# dartBoardV1.net
KiCad netlist of a schematic drawn in EAGLE
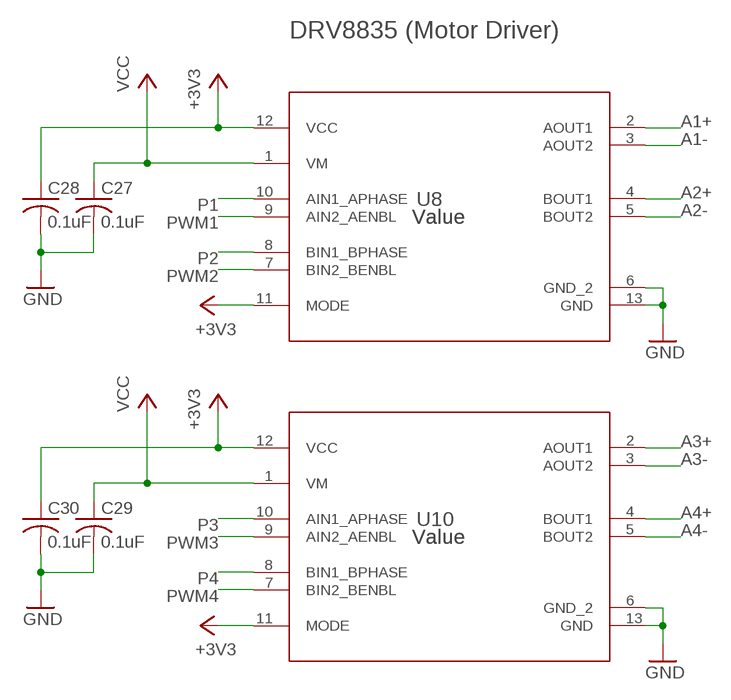
[diagram p0: schematic, sheet 1, part 1 of 2]
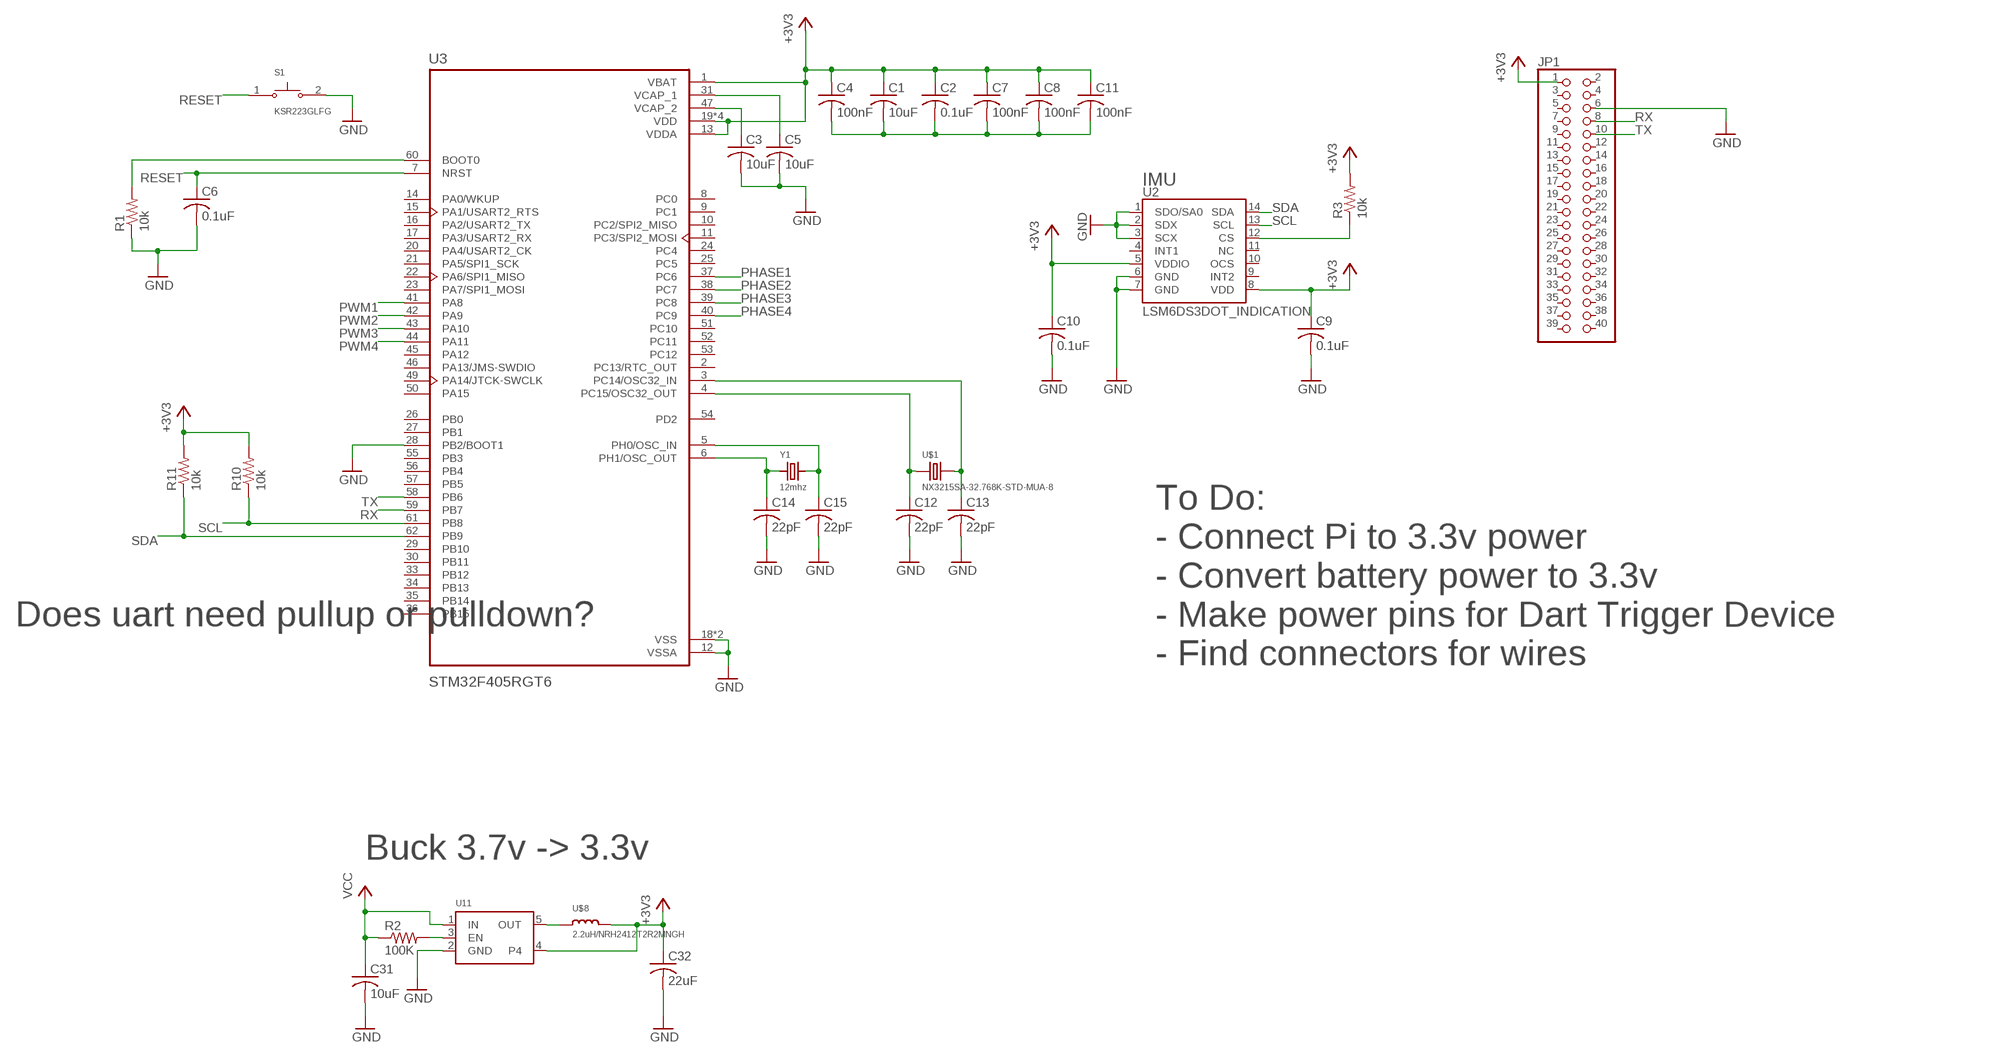
[diagram p1: schematic, sheet 1, part 2 of 2]

(export (version "E")
  (design (tool "Eeschema 10.0.6"))
  (components
    (comp (ref "C1")
      (value "10uF")
      (footprint "eagle-import:C0603")
      (libsource (lib "eagle-import") (part "C-USC0603"))
    )
    (comp (ref "C2")
      (value "0.1uF")
      (footprint "eagle-import:C0603")
      (libsource (lib "eagle-import") (part "C-USC0603"))
    )
    (comp (ref "C3")
      (value "10uF")
      (footprint "eagle-import:C0603")
      (libsource (lib "eagle-import") (part "C-USC0603"))
    )
    (comp (ref "C4")
      (value "100nF")
      (footprint "eagle-import:C0603")
      (libsource (lib "eagle-import") (part "C-USC0603"))
    )
    (comp (ref "C5")
      (value "10uF")
      (footprint "eagle-import:C0603")
      (libsource (lib "eagle-import") (part "C-USC0603"))
    )
    (comp (ref "C6")
      (value "0.1uF")
      (footprint "eagle-import:C0603")
      (libsource (lib "eagle-import") (part "C-USC0603"))
    )
    (comp (ref "C7")
      (value "100nF")
      (footprint "eagle-import:C0603")
      (libsource (lib "eagle-import") (part "C-USC0603"))
    )
    (comp (ref "C8")
      (value "100nF")
      (footprint "eagle-import:C0603")
      (libsource (lib "eagle-import") (part "C-USC0603"))
    )
    (comp (ref "C9")
      (value "0.1uF")
      (footprint "eagle-import:C0603")
      (libsource (lib "eagle-import") (part "C-USC0603"))
    )
    (comp (ref "C10")
      (value "0.1uF")
      (footprint "eagle-import:C0603")
      (libsource (lib "eagle-import") (part "C-USC0603"))
    )
    (comp (ref "C11")
      (value "100nF")
      (footprint "eagle-import:C0603")
      (libsource (lib "eagle-import") (part "C-USC0603"))
    )
    (comp (ref "C12")
      (value "22pF")
      (footprint "eagle-import:C0603")
      (libsource (lib "eagle-import") (part "C-USC0603"))
    )
    (comp (ref "C13")
      (value "22pF")
      (footprint "eagle-import:C0603")
      (libsource (lib "eagle-import") (part "C-USC0603"))
    )
    (comp (ref "C14")
      (value "22pF")
      (footprint "eagle-import:C0603")
      (libsource (lib "eagle-import") (part "C-USC0603"))
    )
    (comp (ref "C15")
      (value "22pF")
      (footprint "eagle-import:C0603")
      (libsource (lib "eagle-import") (part "C-USC0603"))
    )
    (comp (ref "C27")
      (value "0.1uF")
      (footprint "eagle-import:C0603")
      (libsource (lib "eagle-import") (part "C-USC0603"))
    )
    (comp (ref "C28")
      (value "0.1uF")
      (footprint "eagle-import:C0603")
      (libsource (lib "eagle-import") (part "C-USC0603"))
    )
    (comp (ref "C29")
      (value "0.1uF")
      (footprint "eagle-import:C0603")
      (libsource (lib "eagle-import") (part "C-USC0603"))
    )
    (comp (ref "C30")
      (value "0.1uF")
      (footprint "eagle-import:C0603")
      (libsource (lib "eagle-import") (part "C-USC0603"))
    )
    (comp (ref "C31")
      (value "10uF")
      (footprint "eagle-import:C0603")
      (libsource (lib "eagle-import") (part "C-USC0603"))
    )
    (comp (ref "C32")
      (value "22uF")
      (footprint "eagle-import:C0603")
      (libsource (lib "eagle-import") (part "C-USC0603"))
    )
    (comp (ref "JP1")
      (value "PINHD-2X20")
      (footprint "eagle-import:2X20")
      (libsource (lib "eagle-import") (part "PINHD-2X20"))
    )
    (comp (ref "R1")
      (value "10k")
      (footprint "eagle-import:R0603")
      (libsource (lib "eagle-import") (part "R-US_R0603"))
    )
    (comp (ref "R2")
      (value "100K")
      (footprint "eagle-import:R0603")
      (libsource (lib "eagle-import") (part "R-US_R0603"))
    )
    (comp (ref "R3")
      (value "10k")
      (footprint "eagle-import:R0603")
      (libsource (lib "eagle-import") (part "R-US_R0603"))
    )
    (comp (ref "R10")
      (value "10k")
      (footprint "eagle-import:R0603")
      (libsource (lib "eagle-import") (part "R-US_R0603"))
    )
    (comp (ref "R11")
      (value "10k")
      (footprint "eagle-import:R0603")
      (libsource (lib "eagle-import") (part "R-US_R0603"))
    )
    (comp (ref "S1")
      (value "KSR223GLFG")
      (footprint "eagle-import:SW_KSR223GLFG")
      (fields (field (name "DIGI-KEY_PART_NUMBER") "401-1704-1-ND") (field (name "MF") "C&K"))
      (libsource (lib "eagle-import") (part "KSR223GLFG"))
    )
    (comp (ref "U$1")
      (value "NX3215SA-32.768K-STD-MUA-8")
      (footprint "eagle-import:NX3215SA-32.768K-STD-MUA-8")
      (libsource (lib "eagle-import") (part "NX3215SA-32.768K-STD-MUA-8"))
    )
    (comp (ref "U$8")
      (value "2.2uH/NRH2412T2R2MNGH")
      (footprint "eagle-import:MDKK1616T2R2MM")
      (libsource (lib "eagle-import") (part "MDKK1616T2R2MM"))
    )
    (comp (ref "U2")
      (value "LSM6DS3DOT_INDICATION")
      (footprint "eagle-import:LGA14L_DOT_INDICATOR")
      (libsource (lib "eagle-import") (part "LSM6DS3DOT_INDICATION"))
    )
    (comp (ref "U3")
      (value "STM32F405RGT6")
      (footprint "eagle-import:QFP50P1200X1200X160-64N")
      (fields (field (name "DIGI-KEY_PART_NUMBER") "497-11767-ND") (field (name "MF") "STMicroelectronics"))
      (libsource (lib "eagle-import") (part "STM32F405RGT6"))
    )
    (comp (ref "U8")
      (value "Value")
      (footprint "eagle-import:DSS0012A")
      (fields (field (name "MANUFACTURER") "Texas Instruments") (field (name "PARTNUMBER") "DRV8835DSSR"))
      (libsource (lib "eagle-import") (part "DRV8835DSSR"))
    )
    (comp (ref "U10")
      (value "Value")
      (footprint "eagle-import:DSS0012A")
      (fields (field (name "MANUFACTURER") "Texas Instruments") (field (name "PARTNUMBER") "DRV8835DSSR"))
      (libsource (lib "eagle-import") (part "DRV8835DSSR"))
    )
    (comp (ref "U11")
      (value "VREG_SOT23-5")
      (footprint "eagle-import:SOT23-5")
      (libsource (lib "eagle-import") (part "VREG_SOT23-5"))
    )
    (comp (ref "Y1")
      (value "12mhz")
      (footprint "eagle-import:CRYSTAL_2.5X2")
      (libsource (lib "eagle-import") (part "CRYSTAL2.5X2.0MM"))
    )
  )
  (nets
    (net (code "1") (name "+3V3") (class "Default")
      (node (ref "C1") (pin "1") (pinfunction "1_1") (pintype "passive"))
      (node (ref "C10") (pin "1") (pinfunction "1_1") (pintype "passive"))
      (node (ref "C11") (pin "1") (pinfunction "1_1") (pintype "passive"))
      (node (ref "C2") (pin "1") (pinfunction "1_1") (pintype "passive"))
      (node (ref "C28") (pin "1") (pinfunction "1_1") (pintype "passive"))
      (node (ref "C30") (pin "1") (pinfunction "1_1") (pintype "passive"))
      (node (ref "C32") (pin "1") (pinfunction "1_1") (pintype "passive"))
      (node (ref "C4") (pin "1") (pinfunction "1_1") (pintype "passive"))
      (node (ref "C7") (pin "1") (pinfunction "1_1") (pintype "passive"))
      (node (ref "C8") (pin "1") (pinfunction "1_1") (pintype "passive"))
      (node (ref "C9") (pin "1") (pinfunction "1_1") (pintype "passive"))
      (node (ref "JP1") (pin "1") (pinfunction "1_1") (pintype "passive"))
      (node (ref "R10") (pin "2") (pinfunction "2_2") (pintype "passive"))
      (node (ref "R11") (pin "2") (pinfunction "2_2") (pintype "passive"))
      (node (ref "R3") (pin "2") (pinfunction "2_2") (pintype "passive"))
      (node (ref "U$8") (pin "P$2") (pinfunction "2_P$2") (pintype "passive"))
      (node (ref "U10") (pin "11") (pinfunction "MODE_11") (pintype "input"))
      (node (ref "U10") (pin "12") (pinfunction "VCC_12") (pintype "power_in"))
      (node (ref "U11") (pin "4") (pinfunction "P4_4") (pintype "bidirectional"))
      (node (ref "U2") (pin "5") (pinfunction "VDDIO_5") (pintype "bidirectional"))
      (node (ref "U2") (pin "8") (pinfunction "VDD_8") (pintype "bidirectional"))
      (node (ref "U3") (pin "1") (pinfunction "VBAT_1") (pintype "power_in"))
      (node (ref "U3") (pin "13") (pinfunction "VDDA_13") (pintype "power_in"))
      (node (ref "U3") (pin "19") (pinfunction "VDD_19") (pintype "power_in"))
      (node (ref "U3") (pin "32") (pinfunction "VDD_32") (pintype "power_in"))
      (node (ref "U3") (pin "48") (pinfunction "VDD_48") (pintype "power_in"))
      (node (ref "U3") (pin "64") (pinfunction "VDD_64") (pintype "power_in"))
      (node (ref "U8") (pin "11") (pinfunction "MODE_11") (pintype "input"))
      (node (ref "U8") (pin "12") (pinfunction "VCC_12") (pintype "power_in"))
    )
    (net (code "2") (name "/A1+") (class "Default")
      (node (ref "U8") (pin "2") (pinfunction "AOUT1_2") (pintype "output"))
    )
    (net (code "3") (name "/A1-") (class "Default")
      (node (ref "U8") (pin "3") (pinfunction "AOUT2_3") (pintype "output"))
    )
    (net (code "4") (name "/A2+") (class "Default")
      (node (ref "U8") (pin "4") (pinfunction "BOUT1_4") (pintype "output"))
    )
    (net (code "5") (name "/A2-") (class "Default")
      (node (ref "U8") (pin "5") (pinfunction "BOUT2_5") (pintype "output"))
    )
    (net (code "6") (name "/A3+") (class "Default")
      (node (ref "U10") (pin "2") (pinfunction "AOUT1_2") (pintype "output"))
    )
    (net (code "7") (name "/A3-") (class "Default")
      (node (ref "U10") (pin "3") (pinfunction "AOUT2_3") (pintype "output"))
    )
    (net (code "8") (name "/A4+") (class "Default")
      (node (ref "U10") (pin "4") (pinfunction "BOUT1_4") (pintype "output"))
    )
    (net (code "9") (name "/A4-") (class "Default")
      (node (ref "U10") (pin "5") (pinfunction "BOUT2_5") (pintype "output"))
    )
    (net (code "10") (name "/P1") (class "Default")
      (node (ref "U8") (pin "10") (pinfunction "AIN1_APHASE_10") (pintype "input"))
    )
    (net (code "11") (name "/P2") (class "Default")
      (node (ref "U8") (pin "8") (pinfunction "BIN1_BPHASE_8") (pintype "input"))
    )
    (net (code "12") (name "/P3") (class "Default")
      (node (ref "U10") (pin "10") (pinfunction "AIN1_APHASE_10") (pintype "input"))
    )
    (net (code "13") (name "/P4") (class "Default")
      (node (ref "U10") (pin "8") (pinfunction "BIN1_BPHASE_8") (pintype "input"))
    )
    (net (code "14") (name "/PHASE1") (class "Default")
      (node (ref "U3") (pin "37") (pinfunction "PC6_37") (pintype "bidirectional"))
    )
    (net (code "15") (name "/PHASE2") (class "Default")
      (node (ref "U3") (pin "38") (pinfunction "PC7_38") (pintype "bidirectional"))
    )
    (net (code "16") (name "/PHASE3") (class "Default")
      (node (ref "U3") (pin "39") (pinfunction "PC8_39") (pintype "bidirectional"))
    )
    (net (code "17") (name "/PHASE4") (class "Default")
      (node (ref "U3") (pin "40") (pinfunction "PC9_40") (pintype "bidirectional"))
    )
    (net (code "18") (name "/PWM1") (class "Default")
      (node (ref "U3") (pin "41") (pinfunction "PA8_41") (pintype "bidirectional"))
      (node (ref "U8") (pin "9") (pinfunction "AIN2_AENBL_9") (pintype "input"))
    )
    (net (code "19") (name "/PWM2") (class "Default")
      (node (ref "U3") (pin "42") (pinfunction "PA9_42") (pintype "bidirectional"))
      (node (ref "U8") (pin "7") (pinfunction "BIN2_BENBL_7") (pintype "input"))
    )
    (net (code "20") (name "/PWM3") (class "Default")
      (node (ref "U10") (pin "9") (pinfunction "AIN2_AENBL_9") (pintype "input"))
      (node (ref "U3") (pin "43") (pinfunction "PA10_43") (pintype "bidirectional"))
    )
    (net (code "21") (name "/PWM4") (class "Default")
      (node (ref "U10") (pin "7") (pinfunction "BIN2_BENBL_7") (pintype "input"))
      (node (ref "U3") (pin "44") (pinfunction "PA11_44") (pintype "bidirectional"))
    )
    (net (code "22") (name "/RESET") (class "Default")
      (node (ref "C6") (pin "1") (pinfunction "1_1") (pintype "passive"))
      (node (ref "S1") (pin "1") (pinfunction "1_1") (pintype "passive"))
      (node (ref "U3") (pin "7") (pinfunction "NRST_7") (pintype "bidirectional"))
    )
    (net (code "23") (name "/RX") (class "Default")
      (node (ref "JP1") (pin "8") (pinfunction "8_8") (pintype "passive"))
      (node (ref "U3") (pin "59") (pinfunction "PB7_59") (pintype "bidirectional"))
    )
    (net (code "24") (name "/SCL") (class "Default")
      (node (ref "R10") (pin "1") (pinfunction "1_1") (pintype "passive"))
      (node (ref "U2") (pin "13") (pinfunction "SCL_13") (pintype "bidirectional"))
      (node (ref "U3") (pin "61") (pinfunction "PB8_61") (pintype "bidirectional"))
    )
    (net (code "25") (name "/SDA") (class "Default")
      (node (ref "R11") (pin "1") (pinfunction "1_1") (pintype "passive"))
      (node (ref "U2") (pin "14") (pinfunction "SDA_14") (pintype "bidirectional"))
      (node (ref "U3") (pin "62") (pinfunction "PB9_62") (pintype "bidirectional"))
    )
    (net (code "26") (name "/TX") (class "Default")
      (node (ref "JP1") (pin "10") (pinfunction "10_10") (pintype "passive"))
      (node (ref "U3") (pin "58") (pinfunction "PB6_58") (pintype "bidirectional"))
    )
    (net (code "27") (name "GND") (class "Default")
      (node (ref "C10") (pin "2") (pinfunction "2_2") (pintype "passive"))
      (node (ref "C12") (pin "2") (pinfunction "2_2") (pintype "passive"))
      (node (ref "C13") (pin "2") (pinfunction "2_2") (pintype "passive"))
      (node (ref "C14") (pin "2") (pinfunction "2_2") (pintype "passive"))
      (node (ref "C15") (pin "2") (pinfunction "2_2") (pintype "passive"))
      (node (ref "C27") (pin "2") (pinfunction "2_2") (pintype "passive"))
      (node (ref "C28") (pin "2") (pinfunction "2_2") (pintype "passive"))
      (node (ref "C29") (pin "2") (pinfunction "2_2") (pintype "passive"))
      (node (ref "C3") (pin "2") (pinfunction "2_2") (pintype "passive"))
      (node (ref "C30") (pin "2") (pinfunction "2_2") (pintype "passive"))
      (node (ref "C31") (pin "2") (pinfunction "2_2") (pintype "passive"))
      (node (ref "C32") (pin "2") (pinfunction "2_2") (pintype "passive"))
      (node (ref "C5") (pin "2") (pinfunction "2_2") (pintype "passive"))
      (node (ref "C6") (pin "2") (pinfunction "2_2") (pintype "passive"))
      (node (ref "C9") (pin "2") (pinfunction "2_2") (pintype "passive"))
      (node (ref "JP1") (pin "6") (pinfunction "6_6") (pintype "passive"))
      (node (ref "R1") (pin "1") (pinfunction "1_1") (pintype "passive"))
      (node (ref "S1") (pin "2") (pinfunction "2_2") (pintype "passive"))
      (node (ref "U10") (pin "13") (pinfunction "GND_13") (pintype "power_in"))
      (node (ref "U10") (pin "6") (pinfunction "GND_2_6") (pintype "power_in"))
      (node (ref "U11") (pin "2") (pinfunction "GND_2") (pintype "bidirectional"))
      (node (ref "U2") (pin "1") (pinfunction "SDO/SA0_1") (pintype "bidirectional"))
      (node (ref "U2") (pin "2") (pinfunction "SDX_2") (pintype "bidirectional"))
      (node (ref "U2") (pin "3") (pinfunction "SCX_3") (pintype "bidirectional"))
      (node (ref "U2") (pin "6") (pinfunction "GND_6") (pintype "bidirectional"))
      (node (ref "U2") (pin "7") (pinfunction "GND_7") (pintype "bidirectional"))
      (node (ref "U3") (pin "12") (pinfunction "VSSA_12") (pintype "power_in"))
      (node (ref "U3") (pin "18") (pinfunction "VSS_18") (pintype "power_in"))
      (node (ref "U3") (pin "28") (pinfunction "PB2/BOOT1_28") (pintype "bidirectional"))
      (node (ref "U3") (pin "63") (pinfunction "VSS_63") (pintype "power_in"))
      (node (ref "U8") (pin "13") (pinfunction "GND_13") (pintype "power_in"))
      (node (ref "U8") (pin "6") (pinfunction "GND_2_6") (pintype "power_in"))
    )
    (net (code "28") (name "Net-(C1-Pad2)") (class "Default")
      (node (ref "C1") (pin "2") (pinfunction "2_2") (pintype "passive"))
      (node (ref "C11") (pin "2") (pinfunction "2_2") (pintype "passive"))
      (node (ref "C2") (pin "2") (pinfunction "2_2") (pintype "passive"))
      (node (ref "C4") (pin "2") (pinfunction "2_2") (pintype "passive"))
      (node (ref "C7") (pin "2") (pinfunction "2_2") (pintype "passive"))
      (node (ref "C8") (pin "2") (pinfunction "2_2") (pintype "passive"))
    )
    (net (code "29") (name "Net-(U$1-1)") (class "Default")
      (node (ref "C12") (pin "1") (pinfunction "1_1") (pintype "passive"))
      (node (ref "U$1") (pin "P$1") (pinfunction "1_P$1") (pintype "passive"))
      (node (ref "U3") (pin "4") (pinfunction "PC15/OSC32_OUT_4") (pintype "bidirectional"))
    )
    (net (code "30") (name "Net-(U$1-2)") (class "Default")
      (node (ref "C13") (pin "1") (pinfunction "1_1") (pintype "passive"))
      (node (ref "U$1") (pin "P$2") (pinfunction "2_P$2") (pintype "passive"))
      (node (ref "U3") (pin "3") (pinfunction "PC14/OSC32_IN_3") (pintype "bidirectional"))
    )
    (net (code "31") (name "Net-(U$8-1)") (class "Default")
      (node (ref "U$8") (pin "P$1") (pinfunction "1_P$1") (pintype "passive"))
      (node (ref "U11") (pin "5") (pinfunction "OUT_5") (pintype "bidirectional"))
    )
    (net (code "32") (name "Net-(U2-CS)") (class "Default")
      (node (ref "R3") (pin "1") (pinfunction "1_1") (pintype "passive"))
      (node (ref "U2") (pin "12") (pinfunction "CS_12") (pintype "bidirectional"))
    )
    (net (code "33") (name "Net-(U3-BOOT0)") (class "Default")
      (node (ref "R1") (pin "2") (pinfunction "2_2") (pintype "passive"))
      (node (ref "U3") (pin "60") (pinfunction "BOOT0_60") (pintype "bidirectional"))
    )
    (net (code "34") (name "Net-(U3-PH0{slash}OSC_IN)") (class "Default")
      (node (ref "C15") (pin "1") (pinfunction "1_1") (pintype "passive"))
      (node (ref "U3") (pin "5") (pinfunction "PH0/OSC_IN_5") (pintype "bidirectional"))
      (node (ref "Y1") (pin "3") (pinfunction "2_3") (pintype "passive"))
    )
    (net (code "35") (name "Net-(U3-PH1{slash}OSC_OUT)") (class "Default")
      (node (ref "C14") (pin "1") (pinfunction "1_1") (pintype "passive"))
      (node (ref "U3") (pin "6") (pinfunction "PH1/OSC_OUT_6") (pintype "bidirectional"))
      (node (ref "Y1") (pin "1") (pinfunction "1_1") (pintype "passive"))
    )
    (net (code "36") (name "Net-(U3-VCAP_1)") (class "Default")
      (node (ref "C5") (pin "1") (pinfunction "1_1") (pintype "passive"))
      (node (ref "U3") (pin "31") (pinfunction "VCAP_1_31") (pintype "power_in"))
    )
    (net (code "37") (name "Net-(U3-VCAP_2)") (class "Default")
      (node (ref "C3") (pin "1") (pinfunction "1_1") (pintype "passive"))
      (node (ref "U3") (pin "47") (pinfunction "VCAP_2_47") (pintype "power_in"))
    )
    (net (code "38") (name "Net-(U11-EN)") (class "Default")
      (node (ref "R2") (pin "2") (pinfunction "2_2") (pintype "passive"))
      (node (ref "U11") (pin "3") (pinfunction "EN_3") (pintype "bidirectional"))
    )
    (net (code "39") (name "VCC") (class "Default")
      (node (ref "C27") (pin "1") (pinfunction "1_1") (pintype "passive"))
      (node (ref "C29") (pin "1") (pinfunction "1_1") (pintype "passive"))
      (node (ref "C31") (pin "1") (pinfunction "1_1") (pintype "passive"))
      (node (ref "R2") (pin "1") (pinfunction "1_1") (pintype "passive"))
      (node (ref "U10") (pin "1") (pinfunction "VM_1") (pintype "power_in"))
      (node (ref "U11") (pin "1") (pinfunction "IN_1") (pintype "bidirectional"))
      (node (ref "U8") (pin "1") (pinfunction "VM_1") (pintype "power_in"))
    )
    (net (code "40") (name "unconnected-(JP1-Pad2)") (class "Default")
      (node (ref "JP1") (pin "2") (pinfunction "2_2") (pintype "passive"))
    )
    (net (code "41") (name "unconnected-(JP1-Pad3)") (class "Default")
      (node (ref "JP1") (pin "3") (pinfunction "3_3") (pintype "passive"))
    )
    (net (code "42") (name "unconnected-(JP1-Pad4)") (class "Default")
      (node (ref "JP1") (pin "4") (pinfunction "4_4") (pintype "passive"))
    )
    (net (code "43") (name "unconnected-(JP1-Pad5)") (class "Default")
      (node (ref "JP1") (pin "5") (pinfunction "5_5") (pintype "passive"))
    )
    (net (code "44") (name "unconnected-(JP1-Pad7)") (class "Default")
      (node (ref "JP1") (pin "7") (pinfunction "7_7") (pintype "passive"))
    )
    (net (code "45") (name "unconnected-(JP1-Pad9)") (class "Default")
      (node (ref "JP1") (pin "9") (pinfunction "9_9") (pintype "passive"))
    )
    (net (code "46") (name "unconnected-(JP1-Pad11)") (class "Default")
      (node (ref "JP1") (pin "11") (pinfunction "11_11") (pintype "passive"))
    )
    (net (code "47") (name "unconnected-(JP1-Pad12)") (class "Default")
      (node (ref "JP1") (pin "12") (pinfunction "12_12") (pintype "passive"))
    )
    (net (code "48") (name "unconnected-(JP1-Pad13)") (class "Default")
      (node (ref "JP1") (pin "13") (pinfunction "13_13") (pintype "passive"))
    )
    (net (code "49") (name "unconnected-(JP1-Pad14)") (class "Default")
      (node (ref "JP1") (pin "14") (pinfunction "14_14") (pintype "passive"))
    )
    (net (code "50") (name "unconnected-(JP1-Pad15)") (class "Default")
      (node (ref "JP1") (pin "15") (pinfunction "15_15") (pintype "passive"))
    )
    (net (code "51") (name "unconnected-(JP1-Pad16)") (class "Default")
      (node (ref "JP1") (pin "16") (pinfunction "16_16") (pintype "passive"))
    )
    (net (code "52") (name "unconnected-(JP1-Pad17)") (class "Default")
      (node (ref "JP1") (pin "17") (pinfunction "17_17") (pintype "passive"))
    )
    (net (code "53") (name "unconnected-(JP1-Pad18)") (class "Default")
      (node (ref "JP1") (pin "18") (pinfunction "18_18") (pintype "passive"))
    )
    (net (code "54") (name "unconnected-(JP1-Pad19)") (class "Default")
      (node (ref "JP1") (pin "19") (pinfunction "19_19") (pintype "passive"))
    )
    (net (code "55") (name "unconnected-(JP1-Pad20)") (class "Default")
      (node (ref "JP1") (pin "20") (pinfunction "20_20") (pintype "passive"))
    )
    (net (code "56") (name "unconnected-(JP1-Pad21)") (class "Default")
      (node (ref "JP1") (pin "21") (pinfunction "21_21") (pintype "passive"))
    )
    (net (code "57") (name "unconnected-(JP1-Pad22)") (class "Default")
      (node (ref "JP1") (pin "22") (pinfunction "22_22") (pintype "passive"))
    )
    (net (code "58") (name "unconnected-(JP1-Pad23)") (class "Default")
      (node (ref "JP1") (pin "23") (pinfunction "23_23") (pintype "passive"))
    )
    (net (code "59") (name "unconnected-(JP1-Pad24)") (class "Default")
      (node (ref "JP1") (pin "24") (pinfunction "24_24") (pintype "passive"))
    )
    (net (code "60") (name "unconnected-(JP1-Pad25)") (class "Default")
      (node (ref "JP1") (pin "25") (pinfunction "25_25") (pintype "passive"))
    )
    (net (code "61") (name "unconnected-(JP1-Pad26)") (class "Default")
      (node (ref "JP1") (pin "26") (pinfunction "26_26") (pintype "passive"))
    )
    (net (code "62") (name "unconnected-(JP1-Pad27)") (class "Default")
      (node (ref "JP1") (pin "27") (pinfunction "27_27") (pintype "passive"))
    )
    (net (code "63") (name "unconnected-(JP1-Pad28)") (class "Default")
      (node (ref "JP1") (pin "28") (pinfunction "28_28") (pintype "passive"))
    )
    (net (code "64") (name "unconnected-(JP1-Pad29)") (class "Default")
      (node (ref "JP1") (pin "29") (pinfunction "29_29") (pintype "passive"))
    )
    (net (code "65") (name "unconnected-(JP1-Pad30)") (class "Default")
      (node (ref "JP1") (pin "30") (pinfunction "30_30") (pintype "passive"))
    )
    (net (code "66") (name "unconnected-(JP1-Pad31)") (class "Default")
      (node (ref "JP1") (pin "31") (pinfunction "31_31") (pintype "passive"))
    )
    (net (code "67") (name "unconnected-(JP1-Pad32)") (class "Default")
      (node (ref "JP1") (pin "32") (pinfunction "32_32") (pintype "passive"))
    )
    (net (code "68") (name "unconnected-(JP1-Pad33)") (class "Default")
      (node (ref "JP1") (pin "33") (pinfunction "33_33") (pintype "passive"))
    )
    (net (code "69") (name "unconnected-(JP1-Pad34)") (class "Default")
      (node (ref "JP1") (pin "34") (pinfunction "34_34") (pintype "passive"))
    )
    (net (code "70") (name "unconnected-(JP1-Pad35)") (class "Default")
      (node (ref "JP1") (pin "35") (pinfunction "35_35") (pintype "passive"))
    )
    (net (code "71") (name "unconnected-(JP1-Pad36)") (class "Default")
      (node (ref "JP1") (pin "36") (pinfunction "36_36") (pintype "passive"))
    )
    (net (code "72") (name "unconnected-(JP1-Pad37)") (class "Default")
      (node (ref "JP1") (pin "37") (pinfunction "37_37") (pintype "passive"))
    )
    (net (code "73") (name "unconnected-(JP1-Pad38)") (class "Default")
      (node (ref "JP1") (pin "38") (pinfunction "38_38") (pintype "passive"))
    )
    (net (code "74") (name "unconnected-(JP1-Pad39)") (class "Default")
      (node (ref "JP1") (pin "39") (pinfunction "39_39") (pintype "passive"))
    )
    (net (code "75") (name "unconnected-(JP1-Pad40)") (class "Default")
      (node (ref "JP1") (pin "40") (pinfunction "40_40") (pintype "passive"))
    )
    (net (code "76") (name "unconnected-(U2-INT1-Pad4)") (class "Default")
      (node (ref "U2") (pin "4") (pinfunction "INT1_4") (pintype "bidirectional"))
    )
    (net (code "77") (name "unconnected-(U2-INT2-Pad9)") (class "Default")
      (node (ref "U2") (pin "9") (pinfunction "INT2_9") (pintype "bidirectional"))
    )
    (net (code "78") (name "unconnected-(U2-NC-Pad11)") (class "Default")
      (node (ref "U2") (pin "11") (pinfunction "NC_11") (pintype "bidirectional"))
    )
    (net (code "79") (name "unconnected-(U2-OCS-Pad10)") (class "Default")
      (node (ref "U2") (pin "10") (pinfunction "OCS_10") (pintype "bidirectional"))
    )
    (net (code "80") (name "unconnected-(U3-PA0{slash}WKUP-Pad14)") (class "Default")
      (node (ref "U3") (pin "14") (pinfunction "PA0/WKUP_14") (pintype "bidirectional"))
    )
    (net (code "81") (name "unconnected-(U3-PA1{slash}USART2_RTS-Pad15)") (class "Default")
      (node (ref "U3") (pin "15") (pinfunction "PA1/USART2_RTS_15") (pintype "bidirectional"))
    )
    (net (code "82") (name "unconnected-(U3-PA2{slash}USART2_TX-Pad16)") (class "Default")
      (node (ref "U3") (pin "16") (pinfunction "PA2/USART2_TX_16") (pintype "bidirectional"))
    )
    (net (code "83") (name "unconnected-(U3-PA3{slash}USART2_RX-Pad17)") (class "Default")
      (node (ref "U3") (pin "17") (pinfunction "PA3/USART2_RX_17") (pintype "bidirectional"))
    )
    (net (code "84") (name "unconnected-(U3-PA4{slash}USART2_CK-Pad20)") (class "Default")
      (node (ref "U3") (pin "20") (pinfunction "PA4/USART2_CK_20") (pintype "bidirectional"))
    )
    (net (code "85") (name "unconnected-(U3-PA5{slash}SPI1_SCK-Pad21)") (class "Default")
      (node (ref "U3") (pin "21") (pinfunction "PA5/SPI1_SCK_21") (pintype "bidirectional"))
    )
    (net (code "86") (name "unconnected-(U3-PA6{slash}SPI1_MISO-Pad22)") (class "Default")
      (node (ref "U3") (pin "22") (pinfunction "PA6/SPI1_MISO_22") (pintype "bidirectional"))
    )
    (net (code "87") (name "unconnected-(U3-PA7{slash}SPI1_MOSI-Pad23)") (class "Default")
      (node (ref "U3") (pin "23") (pinfunction "PA7/SPI1_MOSI_23") (pintype "bidirectional"))
    )
    (net (code "88") (name "unconnected-(U3-PA12-Pad45)") (class "Default")
      (node (ref "U3") (pin "45") (pinfunction "PA12_45") (pintype "bidirectional"))
    )
    (net (code "89") (name "unconnected-(U3-PA13{slash}JMS-SWDIO-Pad46)") (class "Default")
      (node (ref "U3") (pin "46") (pinfunction "PA13/JMS-SWDIO_46") (pintype "bidirectional"))
    )
    (net (code "90") (name "unconnected-(U3-PA14{slash}JTCK-SWCLK-Pad49)") (class "Default")
      (node (ref "U3") (pin "49") (pinfunction "PA14/JTCK-SWCLK_49") (pintype "bidirectional"))
    )
    (net (code "91") (name "unconnected-(U3-PA15-Pad50)") (class "Default")
      (node (ref "U3") (pin "50") (pinfunction "PA15_50") (pintype "bidirectional"))
    )
    (net (code "92") (name "unconnected-(U3-PB0-Pad26)") (class "Default")
      (node (ref "U3") (pin "26") (pinfunction "PB0_26") (pintype "bidirectional"))
    )
    (net (code "93") (name "unconnected-(U3-PB1-Pad27)") (class "Default")
      (node (ref "U3") (pin "27") (pinfunction "PB1_27") (pintype "bidirectional"))
    )
    (net (code "94") (name "unconnected-(U3-PB3-Pad55)") (class "Default")
      (node (ref "U3") (pin "55") (pinfunction "PB3_55") (pintype "bidirectional"))
    )
    (net (code "95") (name "unconnected-(U3-PB4-Pad56)") (class "Default")
      (node (ref "U3") (pin "56") (pinfunction "PB4_56") (pintype "bidirectional"))
    )
    (net (code "96") (name "unconnected-(U3-PB5-Pad57)") (class "Default")
      (node (ref "U3") (pin "57") (pinfunction "PB5_57") (pintype "bidirectional"))
    )
    (net (code "97") (name "unconnected-(U3-PB10-Pad29)") (class "Default")
      (node (ref "U3") (pin "29") (pinfunction "PB10_29") (pintype "bidirectional"))
    )
    (net (code "98") (name "unconnected-(U3-PB11-Pad30)") (class "Default")
      (node (ref "U3") (pin "30") (pinfunction "PB11_30") (pintype "bidirectional"))
    )
    (net (code "99") (name "unconnected-(U3-PB12-Pad33)") (class "Default")
      (node (ref "U3") (pin "33") (pinfunction "PB12_33") (pintype "bidirectional"))
    )
    (net (code "100") (name "unconnected-(U3-PB13-Pad34)") (class "Default")
      (node (ref "U3") (pin "34") (pinfunction "PB13_34") (pintype "bidirectional"))
    )
    (net (code "101") (name "unconnected-(U3-PB14-Pad35)") (class "Default")
      (node (ref "U3") (pin "35") (pinfunction "PB14_35") (pintype "bidirectional"))
    )
    (net (code "102") (name "unconnected-(U3-PB15-Pad36)") (class "Default")
      (node (ref "U3") (pin "36") (pinfunction "PB15_36") (pintype "bidirectional"))
    )
    (net (code "103") (name "unconnected-(U3-PC0-Pad8)") (class "Default")
      (node (ref "U3") (pin "8") (pinfunction "PC0_8") (pintype "bidirectional"))
    )
    (net (code "104") (name "unconnected-(U3-PC1-Pad9)") (class "Default")
      (node (ref "U3") (pin "9") (pinfunction "PC1_9") (pintype "bidirectional"))
    )
    (net (code "105") (name "unconnected-(U3-PC2{slash}SPI2_MISO-Pad10)") (class "Default")
      (node (ref "U3") (pin "10") (pinfunction "PC2/SPI2_MISO_10") (pintype "bidirectional"))
    )
    (net (code "106") (name "unconnected-(U3-PC3{slash}SPI2_MOSI-Pad11)") (class "Default")
      (node (ref "U3") (pin "11") (pinfunction "PC3/SPI2_MOSI_11") (pintype "bidirectional"))
    )
    (net (code "107") (name "unconnected-(U3-PC4-Pad24)") (class "Default")
      (node (ref "U3") (pin "24") (pinfunction "PC4_24") (pintype "bidirectional"))
    )
    (net (code "108") (name "unconnected-(U3-PC5-Pad25)") (class "Default")
      (node (ref "U3") (pin "25") (pinfunction "PC5_25") (pintype "bidirectional"))
    )
    (net (code "109") (name "unconnected-(U3-PC10-Pad51)") (class "Default")
      (node (ref "U3") (pin "51") (pinfunction "PC10_51") (pintype "bidirectional"))
    )
    (net (code "110") (name "unconnected-(U3-PC11-Pad52)") (class "Default")
      (node (ref "U3") (pin "52") (pinfunction "PC11_52") (pintype "bidirectional"))
    )
    (net (code "111") (name "unconnected-(U3-PC12-Pad53)") (class "Default")
      (node (ref "U3") (pin "53") (pinfunction "PC12_53") (pintype "bidirectional"))
    )
    (net (code "112") (name "unconnected-(U3-PC13{slash}RTC_OUT-Pad2)") (class "Default")
      (node (ref "U3") (pin "2") (pinfunction "PC13/RTC_OUT_2") (pintype "bidirectional"))
    )
    (net (code "113") (name "unconnected-(U3-PD2-Pad54)") (class "Default")
      (node (ref "U3") (pin "54") (pinfunction "PD2_54") (pintype "bidirectional"))
    )
  )
)
